# 528_Wio_Terminal_Rev010000.net
KiCad netlist of a schematic drawn in EAGLE
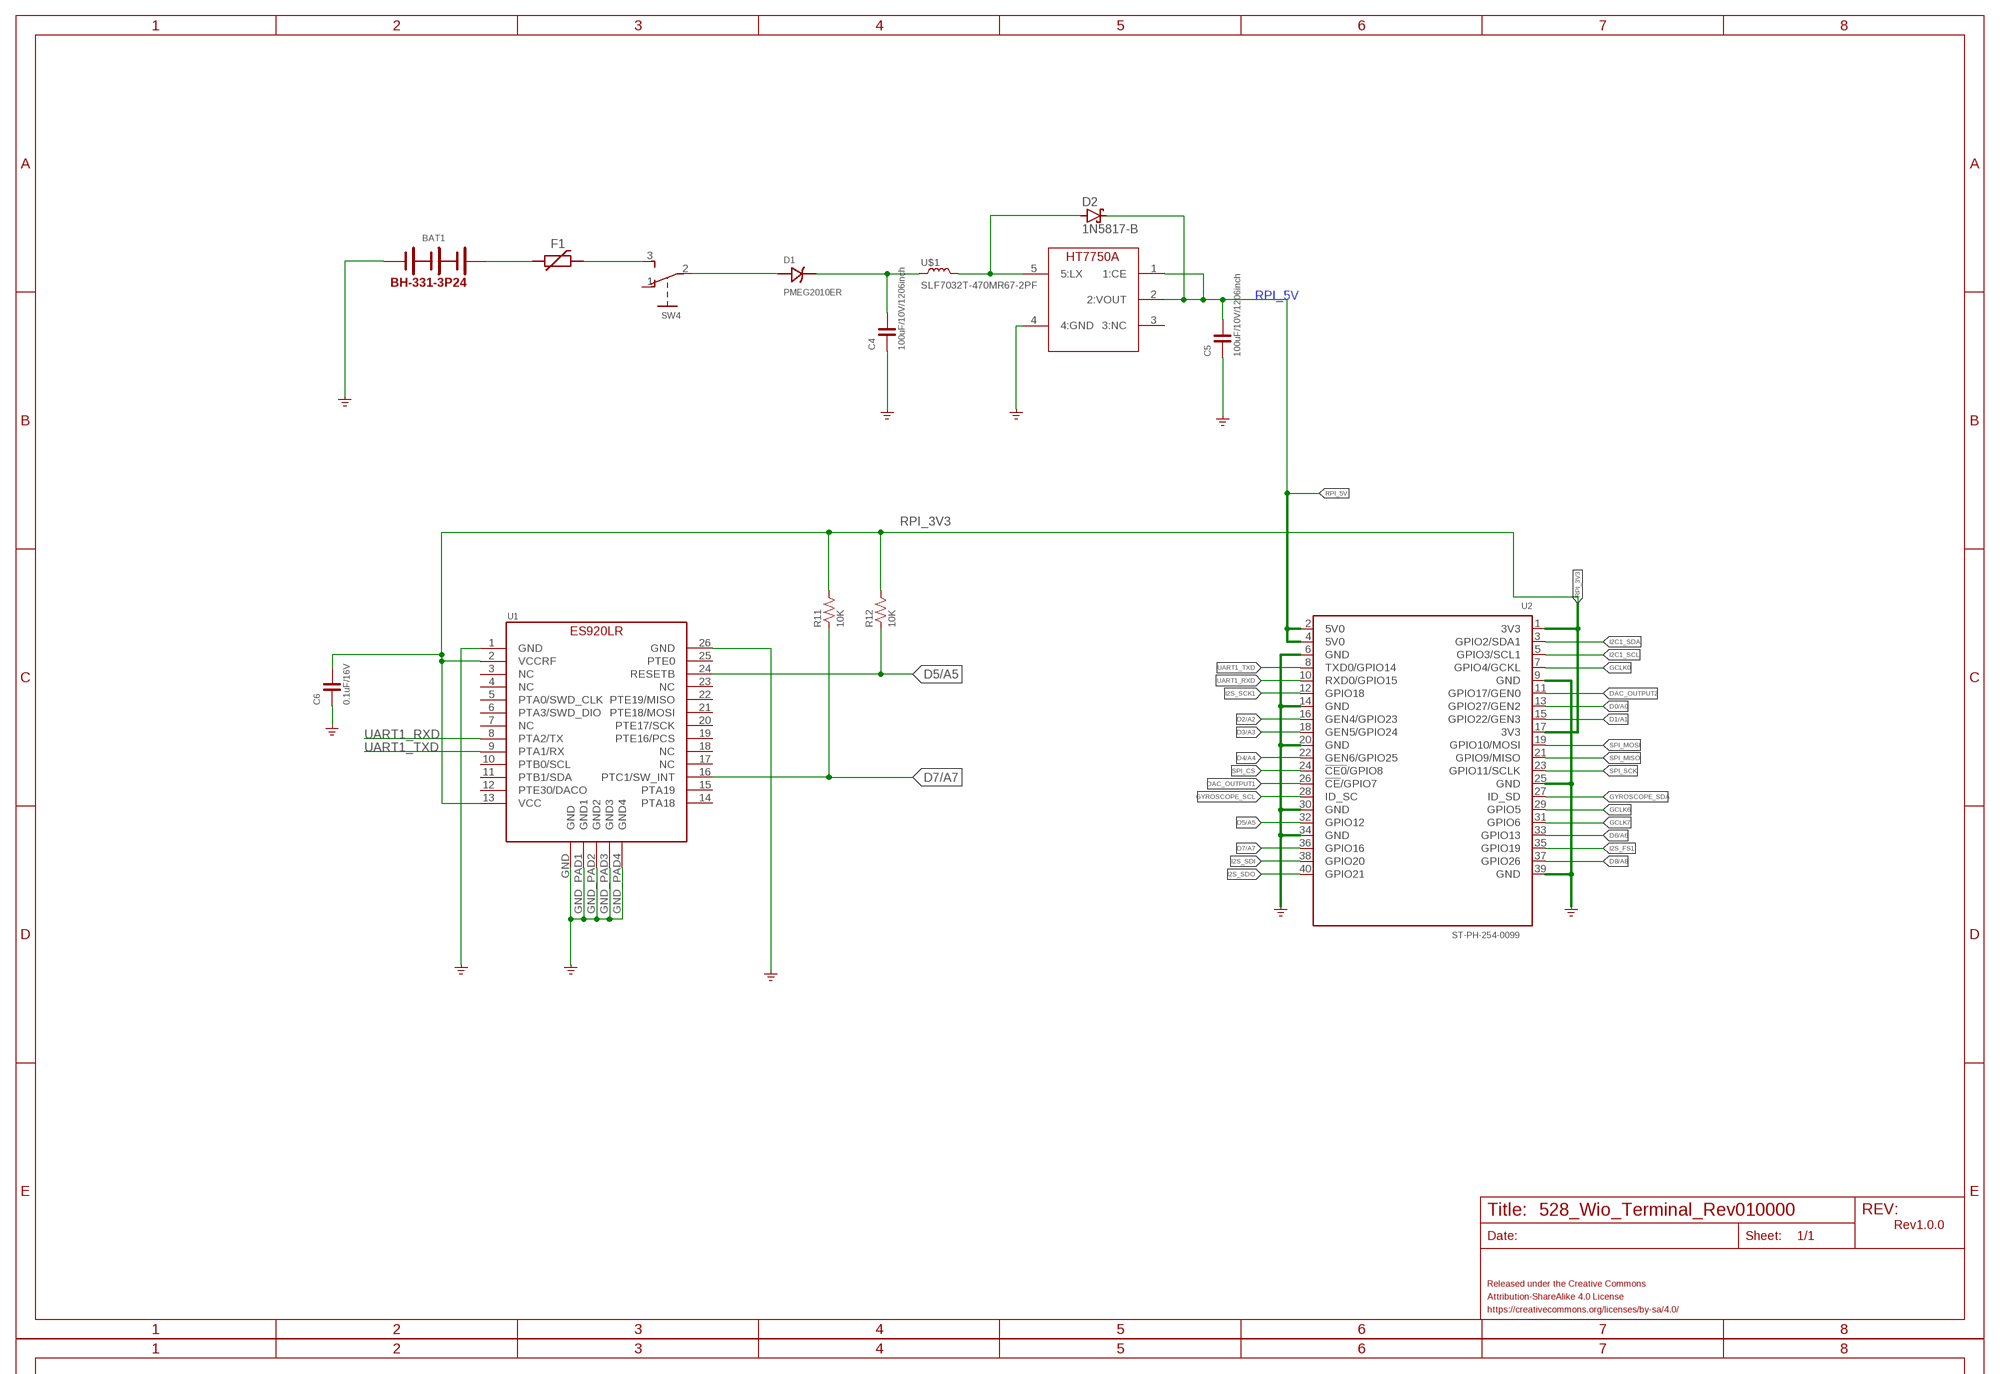
[diagram p0: schematic, sheet 1, part 1 of 2]
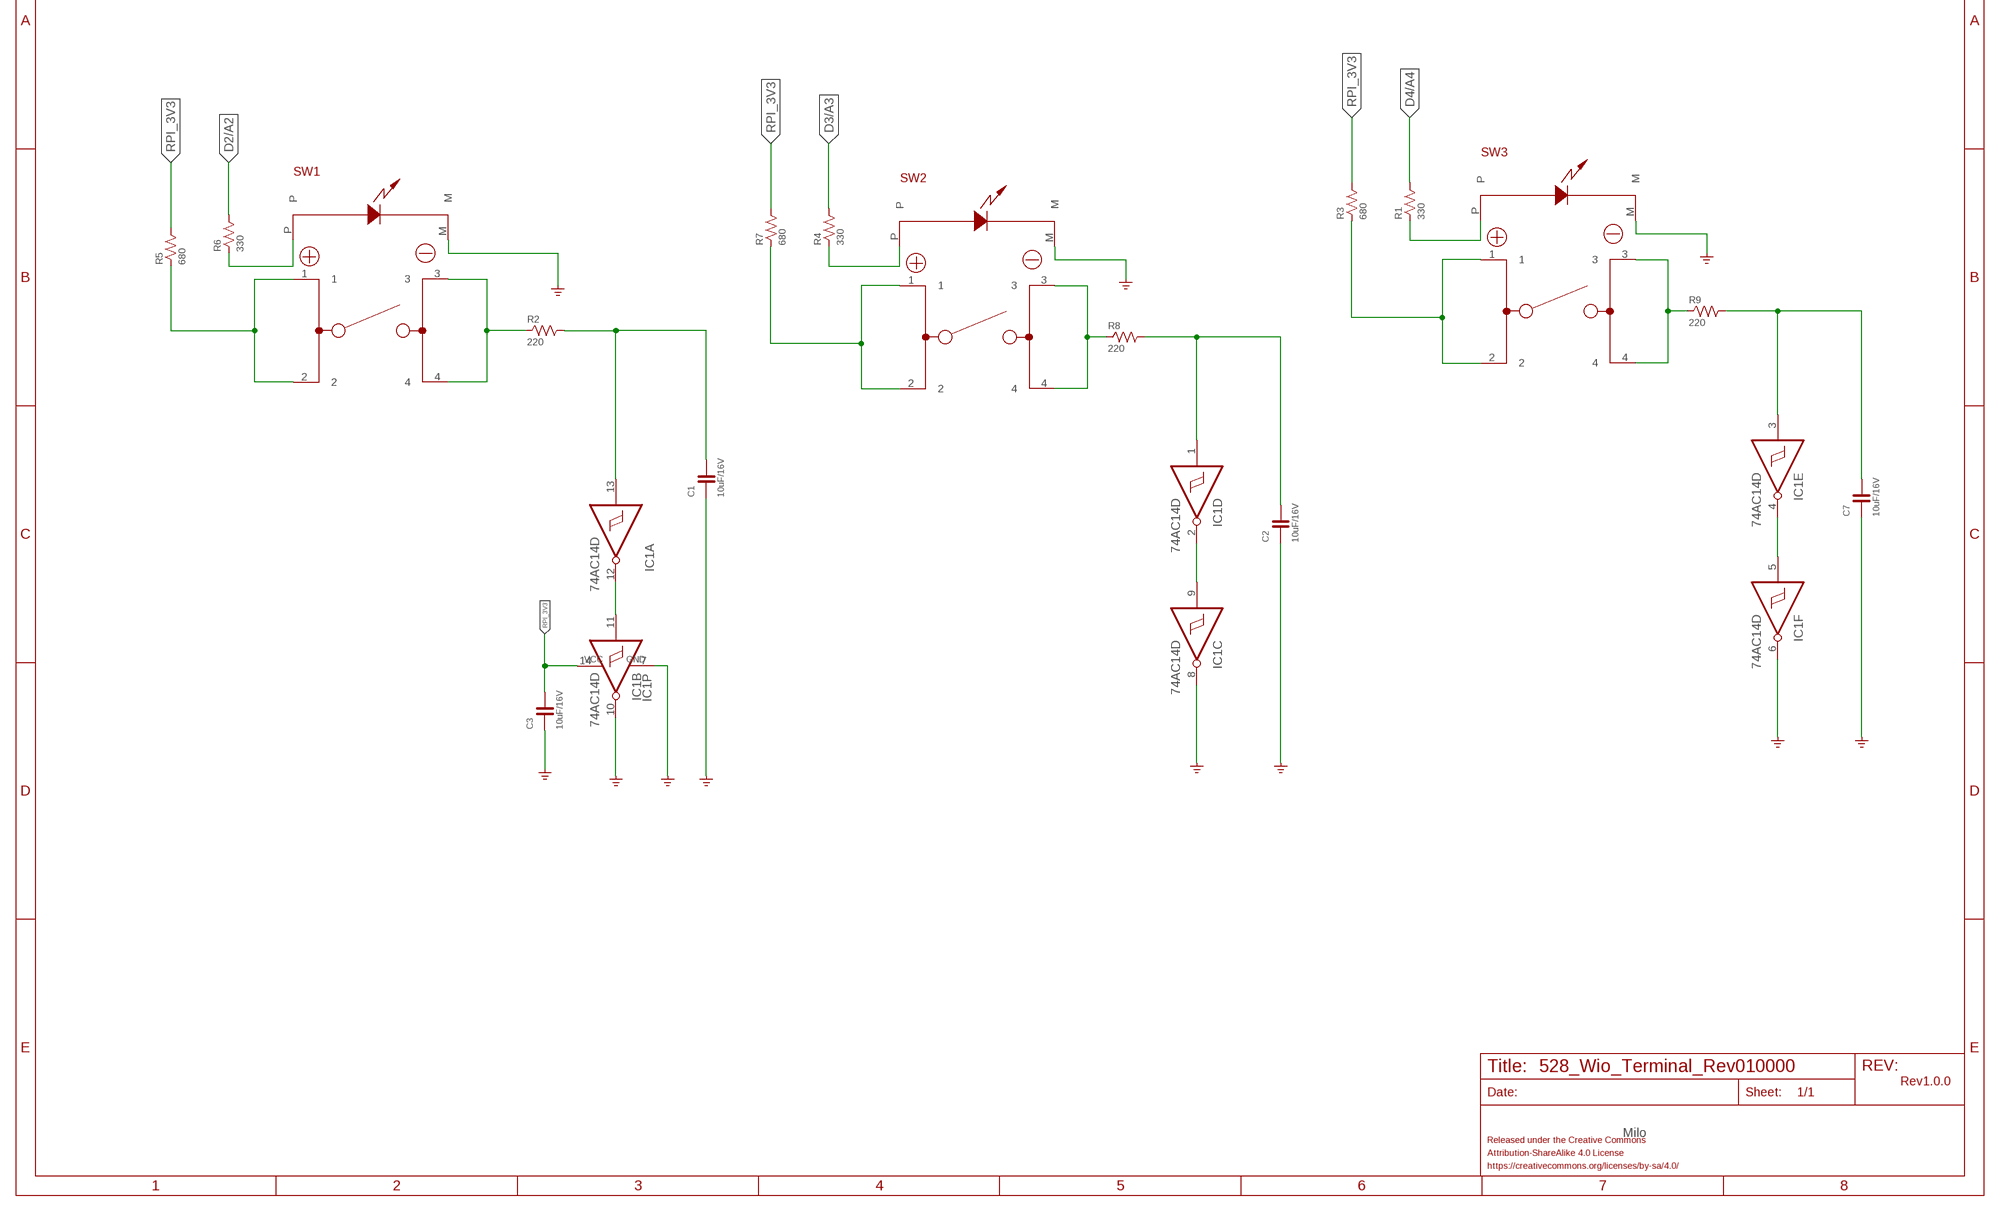
[diagram p1: schematic, sheet 1, part 2 of 2]

(export (version "E")
  (design (tool "Eeschema 10.0.6"))
  (components
    (comp (ref "BAT1")
      (value "BH-331-3P24")
      (footprint "eagle-import:BH-331-3P24")
      (libsource (lib "eagle-import") (part "BH-331-3P24"))
    )
    (comp (ref "C1")
      (value "10uF/16V")
      (footprint "eagle-import:0603")
      (fields (field (name "SPICEPREFIX") "C"))
      (libsource (lib "eagle-import") (part "CAPACITOR-0603"))
    )
    (comp (ref "C2")
      (value "10uF/16V")
      (footprint "eagle-import:0603")
      (fields (field (name "SPICEPREFIX") "C"))
      (libsource (lib "eagle-import") (part "CAPACITOR-0603"))
    )
    (comp (ref "C3")
      (value "10uF/16V")
      (footprint "eagle-import:0603")
      (fields (field (name "SPICEPREFIX") "C"))
      (libsource (lib "eagle-import") (part "CAPACITOR-0603"))
    )
    (comp (ref "C4")
      (value "100uF/10V/1206inch")
      (footprint "eagle-import:1206")
      (libsource (lib "eagle-import") (part "CAPACITOR-1206"))
    )
    (comp (ref "C5")
      (value "100uF/10V/1206inch")
      (footprint "eagle-import:1206")
      (libsource (lib "eagle-import") (part "CAPACITOR-1206"))
    )
    (comp (ref "C6")
      (value "0.1uF/16V")
      (footprint "eagle-import:0603")
      (fields (field (name "SPICEPREFIX") "C"))
      (libsource (lib "eagle-import") (part "CAPACITOR-0603"))
    )
    (comp (ref "C7")
      (value "10uF/16V")
      (footprint "eagle-import:0603")
      (fields (field (name "SPICEPREFIX") "C"))
      (libsource (lib "eagle-import") (part "CAPACITOR-0603"))
    )
    (comp (ref "D1")
      (value "PMEG2010ER")
      (footprint "eagle-import:SOD123W")
      (libsource (lib "eagle-import") (part "PMEG2010ER"))
    )
    (comp (ref "D2")
      (value "1N5817-B")
      (footprint "eagle-import:DO41-7.6")
      (libsource (lib "eagle-import") (part "1N5817-B"))
    )
    (comp (ref "F1")
      (value "POLYSWITCH1206")
      (footprint "eagle-import:1206")
      (libsource (lib "eagle-import") (part "POLYSWITCH1206"))
    )
    (comp (ref "IC1")
      (value "74AC14D")
      (footprint "eagle-import:SO14")
      (fields (field (name "SPICEPREFIX") "I"))
      (libsource (lib "eagle-import") (part "7414DAC"))
    )
    (comp (ref "R1")
      (value "330")
      (footprint "eagle-import:0603")
      (fields (field (name "SPICEPREFIX") "R"))
      (libsource (lib "eagle-import") (part "RESISTOR-0603"))
    )
    (comp (ref "R2")
      (value "220")
      (footprint "eagle-import:0603")
      (fields (field (name "SPICEPREFIX") "R"))
      (libsource (lib "eagle-import") (part "RESISTOR-0603"))
    )
    (comp (ref "R3")
      (value "680")
      (footprint "eagle-import:0603")
      (fields (field (name "SPICEPREFIX") "R"))
      (libsource (lib "eagle-import") (part "RESISTOR-0603"))
    )
    (comp (ref "R4")
      (value "330")
      (footprint "eagle-import:0603")
      (fields (field (name "SPICEPREFIX") "R"))
      (libsource (lib "eagle-import") (part "RESISTOR-0603"))
    )
    (comp (ref "R5")
      (value "680")
      (footprint "eagle-import:0603")
      (fields (field (name "SPICEPREFIX") "R"))
      (libsource (lib "eagle-import") (part "RESISTOR-0603"))
    )
    (comp (ref "R6")
      (value "330")
      (footprint "eagle-import:0603")
      (fields (field (name "SPICEPREFIX") "R"))
      (libsource (lib "eagle-import") (part "RESISTOR-0603"))
    )
    (comp (ref "R7")
      (value "680")
      (footprint "eagle-import:0603")
      (fields (field (name "SPICEPREFIX") "R"))
      (libsource (lib "eagle-import") (part "RESISTOR-0603"))
    )
    (comp (ref "R8")
      (value "220")
      (footprint "eagle-import:0603")
      (fields (field (name "SPICEPREFIX") "R"))
      (libsource (lib "eagle-import") (part "RESISTOR-0603"))
    )
    (comp (ref "R9")
      (value "220")
      (footprint "eagle-import:0603")
      (fields (field (name "SPICEPREFIX") "R"))
      (libsource (lib "eagle-import") (part "RESISTOR-0603"))
    )
    (comp (ref "R11")
      (value "10K")
      (footprint "eagle-import:0603")
      (fields (field (name "SPICEPREFIX") "R"))
      (libsource (lib "eagle-import") (part "RESISTOR-0603"))
    )
    (comp (ref "R12")
      (value "10K")
      (footprint "eagle-import:0603")
      (fields (field (name "SPICEPREFIX") "R"))
      (libsource (lib "eagle-import") (part "RESISTOR-0603"))
    )
    (comp (ref "SW1")
      (value "LTM2-01-L2(RED)")
      (footprint "eagle-import:LTM2")
      (fields (field (name "SPICEPREFIX") "X"))
      (libsource (lib "eagle-import") (part "LTM2-01-L2(RED)"))
    )
    (comp (ref "SW2")
      (value "LTM2-01-L8(YELLOW)")
      (footprint "eagle-import:LTM2")
      (libsource (lib "eagle-import") (part "LTM2-01-L8(YELLOW)"))
    )
    (comp (ref "SW3")
      (value "LTM2-01-L8(YELLOW)")
      (footprint "eagle-import:LTM2")
      (libsource (lib "eagle-import") (part "LTM2-01-L8(YELLOW)"))
    )
    (comp (ref "SW4")
      (value "SLIDE-SSSS810701")
      (footprint "eagle-import:SSSS810701")
      (libsource (lib "eagle-import") (part "SLIDE-SSSS810701"))
    )
    (comp (ref "U$1")
      (value "SLF7032T-470MR67-2PF")
      (footprint "eagle-import:SLF7032T-470MR67-2PF")
      (libsource (lib "eagle-import") (part "SLF7032T-470MR67-2PF"))
    )
    (comp (ref "U$2")
      (value "HT7750A")
      (footprint "eagle-import:SOT-25")
      (libsource (lib "eagle-import") (part "HT7750A"))
    )
    (comp (ref "U1")
      (value "ES920LR")
      (footprint "eagle-import:ES920LR")
      (libsource (lib "eagle-import") (part "ES920LR"))
    )
    (comp (ref "U2")
      (value "ST-PH-254-0099")
      (footprint "eagle-import:H2X20-SMD-2.54-50.8X5MM-LONG")
      (libsource (lib "eagle-import") (part "RPI-ZERO-LONG"))
    )
  )
  (nets
    (net (code "1") (name "D0{slash}A0") (class "Default")
      (node (ref "U2") (pin "13") (pinfunction "GPIO27/GEN2_13") (pintype "bidirectional"))
    )
    (net (code "2") (name "D1{slash}A1") (class "Default")
      (node (ref "U2") (pin "15") (pinfunction "GPIO22/GEN3_15") (pintype "bidirectional"))
    )
    (net (code "3") (name "D2{slash}A2") (class "Default")
      (node (ref "R6") (pin "2") (pinfunction "2_2") (pintype "bidirectional"))
      (node (ref "U2") (pin "16") (pinfunction "GEN4/GPIO23_16") (pintype "bidirectional"))
    )
    (net (code "4") (name "D3{slash}A3") (class "Default")
      (node (ref "R4") (pin "2") (pinfunction "2_2") (pintype "bidirectional"))
      (node (ref "U2") (pin "18") (pinfunction "GEN5/GPIO24_18") (pintype "bidirectional"))
    )
    (net (code "5") (name "D4{slash}A4") (class "Default")
      (node (ref "R1") (pin "2") (pinfunction "2_2") (pintype "bidirectional"))
      (node (ref "U2") (pin "22") (pinfunction "GEN6/GPIO25_22") (pintype "bidirectional"))
    )
    (net (code "6") (name "D5{slash}A5") (class "Default")
      (node (ref "R12") (pin "1") (pinfunction "1_1") (pintype "bidirectional"))
      (node (ref "U1") (pin "24") (pinfunction "RESETB_24") (pintype "bidirectional"))
      (node (ref "U2") (pin "32") (pinfunction "GPIO12_32") (pintype "bidirectional"))
    )
    (net (code "7") (name "D6{slash}A6") (class "Default")
      (node (ref "U2") (pin "33") (pinfunction "GPIO13_33") (pintype "bidirectional"))
    )
    (net (code "8") (name "D7{slash}A7") (class "Default")
      (node (ref "R11") (pin "1") (pinfunction "1_1") (pintype "bidirectional"))
      (node (ref "U1") (pin "16") (pinfunction "PTC1/SW_INT_16") (pintype "bidirectional"))
      (node (ref "U2") (pin "36") (pinfunction "GPIO16_36") (pintype "bidirectional"))
    )
    (net (code "9") (name "D8{slash}A8") (class "Default")
      (node (ref "U2") (pin "37") (pinfunction "GPIO26_37") (pintype "bidirectional"))
    )
    (net (code "10") (name "DAC_OUTPUT1") (class "Default")
      (node (ref "U2") (pin "26") (pinfunction "~{CE}/GPIO7_26") (pintype "bidirectional"))
    )
    (net (code "11") (name "DAC_OUTPUT2") (class "Default")
      (node (ref "U2") (pin "11") (pinfunction "GPIO17/GEN0_11") (pintype "bidirectional"))
    )
    (net (code "12") (name "GCLK0") (class "Default")
      (node (ref "U2") (pin "7") (pinfunction "GPIO4/GCKL_7") (pintype "bidirectional"))
    )
    (net (code "13") (name "GCLK6") (class "Default")
      (node (ref "U2") (pin "29") (pinfunction "GPIO5_29") (pintype "bidirectional"))
    )
    (net (code "14") (name "GCLK7") (class "Default")
      (node (ref "U2") (pin "31") (pinfunction "GPIO6_31") (pintype "bidirectional"))
    )
    (net (code "15") (name "GND_POWER") (class "Default")
      (node (ref "BAT1") (pin "MINUS") (pinfunction "MINUS_MINUS") (pintype "bidirectional"))
      (node (ref "C1") (pin "1") (pinfunction "1_1") (pintype "passive"))
      (node (ref "C2") (pin "1") (pinfunction "1_1") (pintype "passive"))
      (node (ref "C3") (pin "1") (pinfunction "1_1") (pintype "passive"))
      (node (ref "C4") (pin "2") (pinfunction "1_2") (pintype "passive"))
      (node (ref "C5") (pin "2") (pinfunction "1_2") (pintype "passive"))
      (node (ref "C6") (pin "1") (pinfunction "1_1") (pintype "passive"))
      (node (ref "C7") (pin "1") (pinfunction "1_1") (pintype "passive"))
      (node (ref "IC1") (pin "10") (pinfunction "O_10") (pintype "output"))
      (node (ref "IC1") (pin "6") (pinfunction "O_6") (pintype "output"))
      (node (ref "IC1") (pin "7") (pinfunction "GND_7") (pintype "power_in"))
      (node (ref "IC1") (pin "8") (pinfunction "O_8") (pintype "output"))
      (node (ref "SW1") (pin "M") (pinfunction "M_M") (pintype "bidirectional"))
      (node (ref "SW2") (pin "M") (pinfunction "M_M") (pintype "bidirectional"))
      (node (ref "SW3") (pin "M") (pinfunction "M_M") (pintype "bidirectional"))
      (node (ref "U$2") (pin "4") (pinfunction "4:GND_4") (pintype "power_in"))
      (node (ref "U1") (pin "1") (pinfunction "GND_1") (pintype "bidirectional"))
      (node (ref "U1") (pin "26") (pinfunction "GND_26") (pintype "bidirectional"))
      (node (ref "U1") (pin "GND") (pinfunction "GND_GND") (pintype "bidirectional"))
      (node (ref "U1") (pin "GND_PAD1") (pinfunction "GND1_GND_PAD1") (pintype "bidirectional"))
      (node (ref "U1") (pin "GND_PAD2") (pinfunction "GND2_GND_PAD2") (pintype "bidirectional"))
      (node (ref "U1") (pin "GND_PAD3") (pinfunction "GND3_GND_PAD3") (pintype "bidirectional"))
      (node (ref "U1") (pin "GND_PAD4") (pinfunction "GND4_GND_PAD4") (pintype "bidirectional"))
      (node (ref "U2") (pin "14") (pinfunction "GND_14") (pintype "power_in"))
      (node (ref "U2") (pin "20") (pinfunction "GND_20") (pintype "power_in"))
      (node (ref "U2") (pin "25") (pinfunction "GND_25") (pintype "power_in"))
      (node (ref "U2") (pin "30") (pinfunction "GND_30") (pintype "power_in"))
      (node (ref "U2") (pin "34") (pinfunction "GND_34") (pintype "power_in"))
      (node (ref "U2") (pin "39") (pinfunction "GND_39") (pintype "power_in"))
      (node (ref "U2") (pin "6") (pinfunction "GND_6") (pintype "power_in"))
      (node (ref "U2") (pin "9") (pinfunction "GND_9") (pintype "power_in"))
    )
    (net (code "16") (name "GYROSCOPE_SCL") (class "Default")
      (node (ref "U2") (pin "28") (pinfunction "ID_SC_28") (pintype "bidirectional"))
    )
    (net (code "17") (name "GYROSCOPE_SDA") (class "Default")
      (node (ref "U2") (pin "27") (pinfunction "ID_SD_27") (pintype "bidirectional"))
    )
    (net (code "18") (name "I2C1_SCL") (class "Default")
      (node (ref "U2") (pin "5") (pinfunction "GPIO3/SCL1_5") (pintype "bidirectional"))
    )
    (net (code "19") (name "I2C1_SDA") (class "Default")
      (node (ref "U2") (pin "3") (pinfunction "GPIO2/SDA1_3") (pintype "bidirectional"))
    )
    (net (code "20") (name "I2S_FS1") (class "Default")
      (node (ref "U2") (pin "35") (pinfunction "GPIO19_35") (pintype "bidirectional"))
    )
    (net (code "21") (name "I2S_SCK1") (class "Default")
      (node (ref "U2") (pin "12") (pinfunction "GPIO18_12") (pintype "bidirectional"))
    )
    (net (code "22") (name "I2S_SDI") (class "Default")
      (node (ref "U2") (pin "38") (pinfunction "GPIO20_38") (pintype "bidirectional"))
    )
    (net (code "23") (name "I2S_SDO") (class "Default")
      (node (ref "U2") (pin "40") (pinfunction "GPIO21_40") (pintype "bidirectional"))
    )
    (net (code "24") (name "Net-(BAT1-PLUS)") (class "Default")
      (node (ref "BAT1") (pin "PULS") (pinfunction "PLUS_PULS") (pintype "bidirectional"))
      (node (ref "F1") (pin "1") (pinfunction "1_1") (pintype "bidirectional"))
    )
    (net (code "25") (name "Net-(C4-2)") (class "Default")
      (node (ref "C4") (pin "1") (pinfunction "2_1") (pintype "passive"))
      (node (ref "D1") (pin "1") (pinfunction "CATHODE_1") (pintype "bidirectional"))
      (node (ref "U$1") (pin "1") (pinfunction "1_1") (pintype "bidirectional"))
    )
    (net (code "26") (name "Net-(D1-ANODE)") (class "Default")
      (node (ref "D1") (pin "2") (pinfunction "ANODE_2") (pintype "bidirectional"))
      (node (ref "SW4") (pin "2") (pinfunction "2_2") (pintype "passive"))
    )
    (net (code "27") (name "Net-(F1-Pad2)") (class "Default")
      (node (ref "F1") (pin "2") (pinfunction "2_2") (pintype "bidirectional"))
      (node (ref "SW4") (pin "3") (pinfunction "3_3") (pintype "passive"))
    )
    (net (code "28") (name "Net-(IC1A-I)") (class "Default")
      (node (ref "C1") (pin "2") (pinfunction "2_2") (pintype "passive"))
      (node (ref "IC1") (pin "13") (pinfunction "I_13") (pintype "input"))
      (node (ref "R2") (pin "2") (pinfunction "2_2") (pintype "bidirectional"))
    )
    (net (code "29") (name "Net-(IC1A-O)") (class "Default")
      (node (ref "IC1") (pin "11") (pinfunction "I_11") (pintype "input"))
      (node (ref "IC1") (pin "12") (pinfunction "O_12") (pintype "output"))
    )
    (net (code "30") (name "Net-(IC1C-I)") (class "Default")
      (node (ref "IC1") (pin "2") (pinfunction "O_2") (pintype "output"))
      (node (ref "IC1") (pin "9") (pinfunction "I_9") (pintype "input"))
    )
    (net (code "31") (name "Net-(IC1D-I)") (class "Default")
      (node (ref "C2") (pin "2") (pinfunction "2_2") (pintype "passive"))
      (node (ref "IC1") (pin "1") (pinfunction "I_1") (pintype "input"))
      (node (ref "R8") (pin "2") (pinfunction "2_2") (pintype "bidirectional"))
    )
    (net (code "32") (name "Net-(IC1E-I)") (class "Default")
      (node (ref "C7") (pin "2") (pinfunction "2_2") (pintype "passive"))
      (node (ref "IC1") (pin "3") (pinfunction "I_3") (pintype "input"))
      (node (ref "R9") (pin "2") (pinfunction "2_2") (pintype "bidirectional"))
    )
    (net (code "33") (name "Net-(IC1E-O)") (class "Default")
      (node (ref "IC1") (pin "4") (pinfunction "O_4") (pintype "output"))
      (node (ref "IC1") (pin "5") (pinfunction "I_5") (pintype "input"))
    )
    (net (code "34") (name "Net-(IC1G-VCC)") (class "Default")
      (node (ref "C3") (pin "2") (pinfunction "2_2") (pintype "passive"))
      (node (ref "IC1") (pin "14") (pinfunction "VCC_14") (pintype "power_in"))
    )
    (net (code "35") (name "Net-(R1-Pad1)") (class "Default")
      (node (ref "R1") (pin "1") (pinfunction "1_1") (pintype "bidirectional"))
      (node (ref "SW3") (pin "P") (pinfunction "P_P") (pintype "bidirectional"))
    )
    (net (code "36") (name "Net-(R2-Pad1)") (class "Default")
      (node (ref "R2") (pin "1") (pinfunction "1_1") (pintype "bidirectional"))
      (node (ref "SW1") (pin "3") (pinfunction "3_3") (pintype "bidirectional"))
      (node (ref "SW1") (pin "4") (pinfunction "4_4") (pintype "bidirectional"))
    )
    (net (code "37") (name "Net-(R3-Pad1)") (class "Default")
      (node (ref "R3") (pin "1") (pinfunction "1_1") (pintype "bidirectional"))
      (node (ref "SW3") (pin "1") (pinfunction "1_1") (pintype "bidirectional"))
      (node (ref "SW3") (pin "2") (pinfunction "2_2") (pintype "bidirectional"))
    )
    (net (code "38") (name "Net-(R4-Pad1)") (class "Default")
      (node (ref "R4") (pin "1") (pinfunction "1_1") (pintype "bidirectional"))
      (node (ref "SW2") (pin "P") (pinfunction "P_P") (pintype "bidirectional"))
    )
    (net (code "39") (name "Net-(R5-Pad1)") (class "Default")
      (node (ref "R5") (pin "1") (pinfunction "1_1") (pintype "bidirectional"))
      (node (ref "SW1") (pin "1") (pinfunction "1_1") (pintype "bidirectional"))
      (node (ref "SW1") (pin "2") (pinfunction "2_2") (pintype "bidirectional"))
    )
    (net (code "40") (name "Net-(R6-Pad1)") (class "Default")
      (node (ref "R6") (pin "1") (pinfunction "1_1") (pintype "bidirectional"))
      (node (ref "SW1") (pin "P") (pinfunction "P_P") (pintype "bidirectional"))
    )
    (net (code "41") (name "Net-(R7-Pad1)") (class "Default")
      (node (ref "R7") (pin "1") (pinfunction "1_1") (pintype "bidirectional"))
      (node (ref "SW2") (pin "1") (pinfunction "1_1") (pintype "bidirectional"))
      (node (ref "SW2") (pin "2") (pinfunction "2_2") (pintype "bidirectional"))
    )
    (net (code "42") (name "Net-(R8-Pad1)") (class "Default")
      (node (ref "R8") (pin "1") (pinfunction "1_1") (pintype "bidirectional"))
      (node (ref "SW2") (pin "3") (pinfunction "3_3") (pintype "bidirectional"))
      (node (ref "SW2") (pin "4") (pinfunction "4_4") (pintype "bidirectional"))
    )
    (net (code "43") (name "Net-(R9-Pad1)") (class "Default")
      (node (ref "R9") (pin "1") (pinfunction "1_1") (pintype "bidirectional"))
      (node (ref "SW3") (pin "3") (pinfunction "3_3") (pintype "bidirectional"))
      (node (ref "SW3") (pin "4") (pinfunction "4_4") (pintype "bidirectional"))
    )
    (net (code "44") (name "Net-(U$2-5:LX)") (class "Default")
      (node (ref "D2") (pin "A") (pinfunction "A_A") (pintype "passive"))
      (node (ref "U$1") (pin "2") (pinfunction "2_2") (pintype "bidirectional"))
      (node (ref "U$2") (pin "5") (pinfunction "5:LX_5") (pintype "input"))
    )
    (net (code "45") (name "RPI_3V3") (class "Default")
      (node (ref "C6") (pin "2") (pinfunction "2_2") (pintype "passive"))
      (node (ref "R11") (pin "2") (pinfunction "2_2") (pintype "bidirectional"))
      (node (ref "R12") (pin "2") (pinfunction "2_2") (pintype "bidirectional"))
      (node (ref "R3") (pin "2") (pinfunction "2_2") (pintype "bidirectional"))
      (node (ref "R5") (pin "2") (pinfunction "2_2") (pintype "bidirectional"))
      (node (ref "R7") (pin "2") (pinfunction "2_2") (pintype "bidirectional"))
      (node (ref "U1") (pin "13") (pinfunction "VCC_13") (pintype "bidirectional"))
      (node (ref "U1") (pin "2") (pinfunction "VCCRF_2") (pintype "bidirectional"))
      (node (ref "U2") (pin "1") (pinfunction "3V3_1") (pintype "power_in"))
      (node (ref "U2") (pin "17") (pinfunction "3V3_17") (pintype "power_in"))
    )
    (net (code "46") (name "RPI_5V") (class "Default")
      (node (ref "C5") (pin "1") (pinfunction "2_1") (pintype "passive"))
      (node (ref "D2") (pin "C") (pinfunction "C_C") (pintype "passive"))
      (node (ref "U$2") (pin "1") (pinfunction "1:CE_1") (pintype "input"))
      (node (ref "U$2") (pin "2") (pinfunction "2:VOUT_2") (pintype "power_in"))
      (node (ref "U2") (pin "2") (pinfunction "5V0_2") (pintype "power_in"))
      (node (ref "U2") (pin "4") (pinfunction "5V0_4") (pintype "power_in"))
    )
    (net (code "47") (name "SPI_CS") (class "Default")
      (node (ref "U2") (pin "24") (pinfunction "~{CE0}/GPIO8_24") (pintype "bidirectional"))
    )
    (net (code "48") (name "SPI_MISO") (class "Default")
      (node (ref "U2") (pin "21") (pinfunction "GPIO9/MISO_21") (pintype "bidirectional"))
    )
    (net (code "49") (name "SPI_MOSI") (class "Default")
      (node (ref "U2") (pin "19") (pinfunction "GPIO10/MOSI_19") (pintype "bidirectional"))
    )
    (net (code "50") (name "SPI_SCK") (class "Default")
      (node (ref "U2") (pin "23") (pinfunction "GPIO11/SCLK_23") (pintype "bidirectional"))
    )
    (net (code "51") (name "UART1_RXD") (class "Default")
      (node (ref "U1") (pin "8") (pinfunction "PTA2/TX_8") (pintype "bidirectional"))
      (node (ref "U2") (pin "10") (pinfunction "RXD0/GPIO15_10") (pintype "bidirectional"))
    )
    (net (code "52") (name "UART1_TXD") (class "Default")
      (node (ref "U1") (pin "9") (pinfunction "PTA1/RX_9") (pintype "bidirectional"))
      (node (ref "U2") (pin "8") (pinfunction "TXD0/GPIO14_8") (pintype "bidirectional"))
    )
    (net (code "53") (name "unconnected-(SW4-Pad1)") (class "Default")
      (node (ref "SW4") (pin "1") (pinfunction "1_1") (pintype "passive"))
    )
    (net (code "54") (name "unconnected-(U$2-3:NC-Pad3)") (class "Default")
      (node (ref "U$2") (pin "3") (pinfunction "3:NC_3") (pintype "no_connect"))
    )
    (net (code "55") (name "unconnected-(U1-NC-Pad3)") (class "Default")
      (node (ref "U1") (pin "3") (pinfunction "NC_3") (pintype "bidirectional"))
    )
    (net (code "56") (name "unconnected-(U1-NC-Pad4)") (class "Default")
      (node (ref "U1") (pin "4") (pinfunction "NC_4") (pintype "bidirectional"))
    )
    (net (code "57") (name "unconnected-(U1-NC-Pad7)") (class "Default")
      (node (ref "U1") (pin "7") (pinfunction "NC_7") (pintype "bidirectional"))
    )
    (net (code "58") (name "unconnected-(U1-NC-Pad17)") (class "Default")
      (node (ref "U1") (pin "17") (pinfunction "NC_17") (pintype "bidirectional"))
    )
    (net (code "59") (name "unconnected-(U1-NC-Pad18)") (class "Default")
      (node (ref "U1") (pin "18") (pinfunction "NC_18") (pintype "bidirectional"))
    )
    (net (code "60") (name "unconnected-(U1-NC-Pad23)") (class "Default")
      (node (ref "U1") (pin "23") (pinfunction "NC_23") (pintype "bidirectional"))
    )
    (net (code "61") (name "unconnected-(U1-PTA0{slash}SWD_CLK-Pad5)") (class "Default")
      (node (ref "U1") (pin "5") (pinfunction "PTA0/SWD_CLK_5") (pintype "bidirectional"))
    )
    (net (code "62") (name "unconnected-(U1-PTA3{slash}SWD_DIO-Pad6)") (class "Default")
      (node (ref "U1") (pin "6") (pinfunction "PTA3/SWD_DIO_6") (pintype "bidirectional"))
    )
    (net (code "63") (name "unconnected-(U1-PTA18-Pad14)") (class "Default")
      (node (ref "U1") (pin "14") (pinfunction "PTA18_14") (pintype "bidirectional"))
    )
    (net (code "64") (name "unconnected-(U1-PTA19-Pad15)") (class "Default")
      (node (ref "U1") (pin "15") (pinfunction "PTA19_15") (pintype "bidirectional"))
    )
    (net (code "65") (name "unconnected-(U1-PTB0{slash}SCL-Pad10)") (class "Default")
      (node (ref "U1") (pin "10") (pinfunction "PTB0/SCL_10") (pintype "bidirectional"))
    )
    (net (code "66") (name "unconnected-(U1-PTB1{slash}SDA-Pad11)") (class "Default")
      (node (ref "U1") (pin "11") (pinfunction "PTB1/SDA_11") (pintype "bidirectional"))
    )
    (net (code "67") (name "unconnected-(U1-PTE0-Pad25)") (class "Default")
      (node (ref "U1") (pin "25") (pinfunction "PTE0_25") (pintype "bidirectional"))
    )
    (net (code "68") (name "unconnected-(U1-PTE16{slash}PCS-Pad19)") (class "Default")
      (node (ref "U1") (pin "19") (pinfunction "PTE16/PCS_19") (pintype "bidirectional"))
    )
    (net (code "69") (name "unconnected-(U1-PTE17{slash}SCK-Pad20)") (class "Default")
      (node (ref "U1") (pin "20") (pinfunction "PTE17/SCK_20") (pintype "bidirectional"))
    )
    (net (code "70") (name "unconnected-(U1-PTE18{slash}MOSI-Pad21)") (class "Default")
      (node (ref "U1") (pin "21") (pinfunction "PTE18/MOSI_21") (pintype "bidirectional"))
    )
    (net (code "71") (name "unconnected-(U1-PTE19{slash}MISO-Pad22)") (class "Default")
      (node (ref "U1") (pin "22") (pinfunction "PTE19/MISO_22") (pintype "bidirectional"))
    )
    (net (code "72") (name "unconnected-(U1-PTE30{slash}DACO-Pad12)") (class "Default")
      (node (ref "U1") (pin "12") (pinfunction "PTE30/DACO_12") (pintype "bidirectional"))
    )
  )
)
